# Analouge.net
KiCad netlist of a schematic drawn in Altium Designer
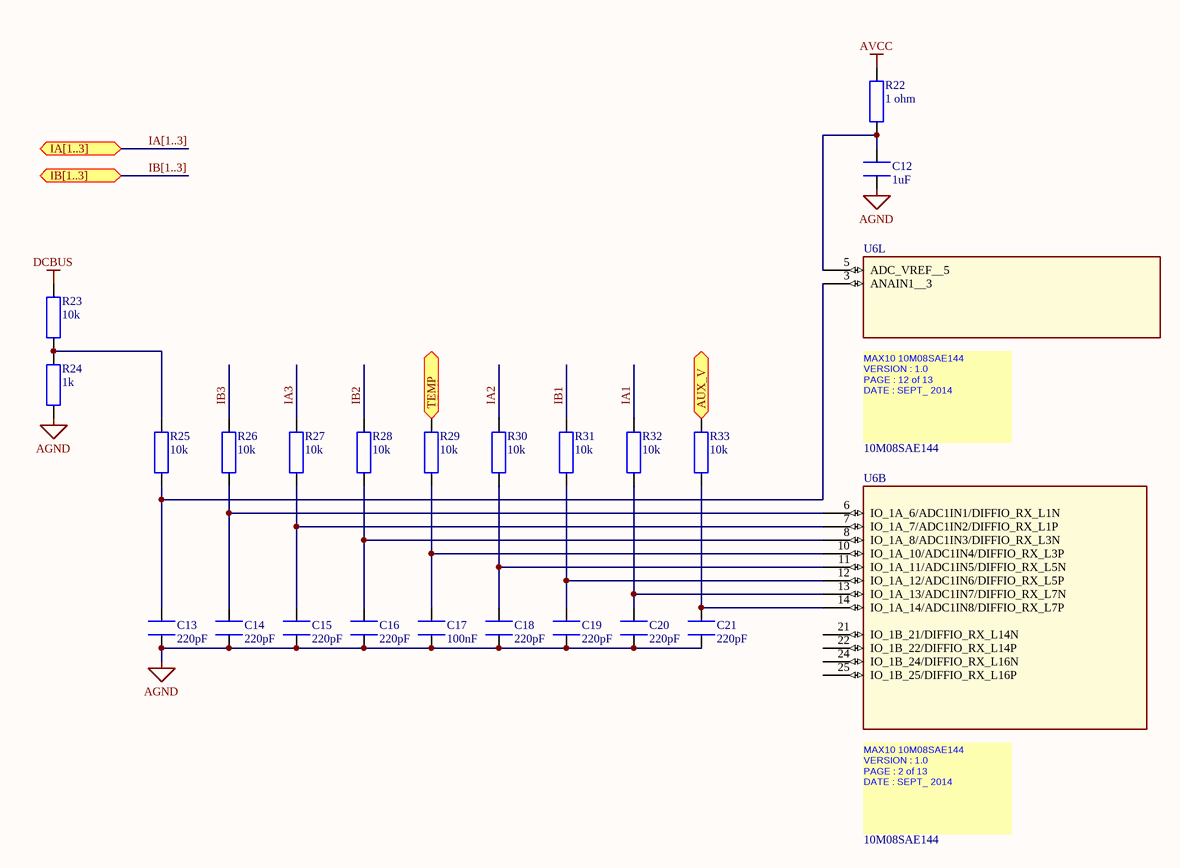
[diagram p0: Analouge.SchDoc]

(export (version "E")
  (design (tool "Eeschema 10.0.6"))
  (components
    (comp (ref "C12")
      (value "1uF")
      (footprint "1608[0603]")
      (description "CAP, MLCC, X5R, 1UF, 16V, 0603")
      (fields (field (name "Comment") "MC0603X105K160"))
      (libsource (lib "CustomComponents") (part "MC0603X105K160"))
    )
    (comp (ref "C13")
      (value "220pF")
      (footprint "1608[0603]")
      (description "CAP, MLCC, C0G/NP0, 220PF, 50V, 0603")
      (fields (field (name "Comment") "MC0603N221J500CT"))
      (libsource (lib "CustomComponents") (part "MC0603N221J500CT"))
    )
    (comp (ref "C14")
      (value "220pF")
      (footprint "1608[0603]")
      (description "CAP, MLCC, C0G/NP0, 220PF, 50V, 0603")
      (fields (field (name "Comment") "MC0603N221J500CT"))
      (libsource (lib "CustomComponents") (part "MC0603N221J500CT"))
    )
    (comp (ref "C15")
      (value "220pF")
      (footprint "1608[0603]")
      (description "CAP, MLCC, C0G/NP0, 220PF, 50V, 0603")
      (fields (field (name "Comment") "MC0603N221J500CT"))
      (libsource (lib "CustomComponents") (part "MC0603N221J500CT"))
    )
    (comp (ref "C16")
      (value "220pF")
      (footprint "1608[0603]")
      (description "CAP, MLCC, C0G/NP0, 220PF, 50V, 0603")
      (fields (field (name "Comment") "MC0603N221J500CT"))
      (libsource (lib "CustomComponents") (part "MC0603N221J500CT"))
    )
    (comp (ref "C17")
      (value "100nF")
      (footprint "1608[0603]")
      (description "CAP, MLCC, X7R, 100NF, 16V, 0603")
      (fields (field (name "Comment") "MC0603B104K160CT"))
      (libsource (lib "CustomComponents") (part "MC0603B104K160CT"))
    )
    (comp (ref "C18")
      (value "220pF")
      (footprint "1608[0603]")
      (description "CAP, MLCC, C0G/NP0, 220PF, 50V, 0603")
      (fields (field (name "Comment") "MC0603N221J500CT"))
      (libsource (lib "CustomComponents") (part "MC0603N221J500CT"))
    )
    (comp (ref "C19")
      (value "220pF")
      (footprint "1608[0603]")
      (description "CAP, MLCC, C0G/NP0, 220PF, 50V, 0603")
      (fields (field (name "Comment") "MC0603N221J500CT"))
      (libsource (lib "CustomComponents") (part "MC0603N221J500CT"))
    )
    (comp (ref "C20")
      (value "220pF")
      (footprint "1608[0603]")
      (description "CAP, MLCC, C0G/NP0, 220PF, 50V, 0603")
      (fields (field (name "Comment") "MC0603N221J500CT"))
      (libsource (lib "CustomComponents") (part "MC0603N221J500CT"))
    )
    (comp (ref "C21")
      (value "220pF")
      (footprint "1608[0603]")
      (description "CAP, MLCC, C0G/NP0, 220PF, 50V, 0603")
      (fields (field (name "Comment") "MC0603N221J500CT"))
      (libsource (lib "CustomComponents") (part "MC0603N221J500CT"))
    )
    (comp (ref "R22")
      (value "1 ohm")
      (footprint "RESC1608X55N")
      (description "RES, THICK FILM, 1OHM, 1%, 0.1W")
      (fields (field (name "Comment") "MCWR06W1R00FTL"))
      (libsource (lib "CustomComponents") (part "MCWR06W1R00FTL"))
    )
    (comp (ref "R23")
      (value "10k")
      (footprint "RESC1608X06L")
      (description "Resistor, 10k, 0603")
      (fields (field (name "Comment") "MCMR06X1002FTL"))
      (libsource (lib "CustomComponents") (part "MCMR06X1002FTL"))
    )
    (comp (ref "R24")
      (value "1k")
      (footprint "RESC1608X55N")
      (description "RESISTOR, CERAMIC, 1K, 0.1W, 1%")
      (fields (field (name "Comment") "MCMR06X1001FTL"))
      (libsource (lib "CustomComponents") (part "MCMR06X1001FTL"))
    )
    (comp (ref "R25")
      (value "10k")
      (footprint "RESC1608X06L")
      (description "Resistor, 10k, 0603")
      (fields (field (name "Comment") "MCMR06X1002FTL"))
      (libsource (lib "CustomComponents") (part "MCMR06X1002FTL"))
    )
    (comp (ref "R26")
      (value "10k")
      (footprint "RESC1608X06L")
      (description "Resistor, 10k, 0603")
      (fields (field (name "Comment") "MCMR06X1002FTL"))
      (libsource (lib "CustomComponents") (part "MCMR06X1002FTL"))
    )
    (comp (ref "R27")
      (value "10k")
      (footprint "RESC1608X06L")
      (description "Resistor, 10k, 0603")
      (fields (field (name "Comment") "MCMR06X1002FTL"))
      (libsource (lib "CustomComponents") (part "MCMR06X1002FTL"))
    )
    (comp (ref "R28")
      (value "10k")
      (footprint "RESC1608X06L")
      (description "Resistor, 10k, 0603")
      (fields (field (name "Comment") "MCMR06X1002FTL"))
      (libsource (lib "CustomComponents") (part "MCMR06X1002FTL"))
    )
    (comp (ref "R29")
      (value "10k")
      (footprint "RESC1608X06L")
      (description "Resistor, 10k, 0603")
      (fields (field (name "Comment") "MCMR06X1002FTL"))
      (libsource (lib "CustomComponents") (part "MCMR06X1002FTL"))
    )
    (comp (ref "R30")
      (value "10k")
      (footprint "RESC1608X06L")
      (description "Resistor, 10k, 0603")
      (fields (field (name "Comment") "MCMR06X1002FTL"))
      (libsource (lib "CustomComponents") (part "MCMR06X1002FTL"))
    )
    (comp (ref "R31")
      (value "10k")
      (footprint "RESC1608X06L")
      (description "Resistor, 10k, 0603")
      (fields (field (name "Comment") "MCMR06X1002FTL"))
      (libsource (lib "CustomComponents") (part "MCMR06X1002FTL"))
    )
    (comp (ref "R32")
      (value "10k")
      (footprint "RESC1608X06L")
      (description "Resistor, 10k, 0603")
      (fields (field (name "Comment") "MCMR06X1002FTL"))
      (libsource (lib "CustomComponents") (part "MCMR06X1002FTL"))
    )
    (comp (ref "R33")
      (value "10k")
      (footprint "RESC1608X06L")
      (description "Resistor, 10k, 0603")
      (fields (field (name "Comment") "MCMR06X1002FTL"))
      (libsource (lib "CustomComponents") (part "MCMR06X1002FTL"))
    )
    (comp (ref "U6")
      (value "10M08SAE144")
      (footprint "SQFP50P2200X2200X165_HS-145N")
      (libsource (lib "10M08SAREVERSIONTEST_Library") (part "10M08SAE144"))
    )
  )
  (nets
    (net (code "1") (name "/AUX_V") (class "Default")
      (node (ref "R33") (pin "2") (pinfunction "0_2") (pintype "passive"))
    )
    (net (code "2") (name "/IA1") (class "Default")
      (node (ref "R32") (pin "2") (pinfunction "0_2") (pintype "passive"))
    )
    (net (code "3") (name "/IA2") (class "Default")
      (node (ref "R30") (pin "2") (pinfunction "0_2") (pintype "passive"))
    )
    (net (code "4") (name "/IA3") (class "Default")
      (node (ref "R27") (pin "2") (pinfunction "0_2") (pintype "passive"))
    )
    (net (code "6") (name "/IB1") (class "Default")
      (node (ref "R31") (pin "2") (pinfunction "0_2") (pintype "passive"))
    )
    (net (code "7") (name "/IB2") (class "Default")
      (node (ref "R28") (pin "2") (pinfunction "0_2") (pintype "passive"))
    )
    (net (code "8") (name "/IB3") (class "Default")
      (node (ref "R26") (pin "2") (pinfunction "0_2") (pintype "passive"))
    )
    (net (code "10") (name "/TEMP") (class "Default")
      (node (ref "R29") (pin "2") (pinfunction "0_2") (pintype "passive"))
    )
    (net (code "11") (name "AGND") (class "Default")
      (node (ref "C12") (pin "1") (pinfunction "1_1") (pintype "passive"))
      (node (ref "C13") (pin "1") (pinfunction "1_1") (pintype "passive"))
      (node (ref "C14") (pin "1") (pinfunction "1_1") (pintype "passive"))
      (node (ref "C15") (pin "1") (pinfunction "1_1") (pintype "passive"))
      (node (ref "C16") (pin "1") (pinfunction "1_1") (pintype "passive"))
      (node (ref "C17") (pin "1") (pinfunction "1_1") (pintype "passive"))
      (node (ref "C18") (pin "1") (pinfunction "1_1") (pintype "passive"))
      (node (ref "C19") (pin "1") (pinfunction "1_1") (pintype "passive"))
      (node (ref "C20") (pin "1") (pinfunction "1_1") (pintype "passive"))
      (node (ref "C21") (pin "1") (pinfunction "1_1") (pintype "passive"))
      (node (ref "R24") (pin "1") (pinfunction "0_1") (pintype "passive"))
    )
    (net (code "12") (name "AVCC") (class "Default")
      (node (ref "R22") (pin "2") (pinfunction "0_2") (pintype "passive"))
    )
    (net (code "13") (name "DCBUS") (class "Default")
      (node (ref "R23") (pin "2") (pinfunction "0_2") (pintype "passive"))
    )
    (net (code "14") (name "Net-(R23-0-Pad1)") (class "Default")
      (node (ref "R23") (pin "1") (pinfunction "0_1") (pintype "passive"))
      (node (ref "R24") (pin "2") (pinfunction "0_2") (pintype "passive"))
      (node (ref "R25") (pin "2") (pinfunction "0_2") (pintype "passive"))
    )
    (net (code "15") (name "Net-(U6B-IO_1A_6{slash}ADC1IN1{slash}DIFFIO_RX_L1N)") (class "Default")
      (node (ref "C14") (pin "2") (pinfunction "2_2") (pintype "passive"))
      (node (ref "R26") (pin "1") (pinfunction "0_1") (pintype "passive"))
      (node (ref "U6") (pin "6") (pinfunction "IO_1A_6/ADC1IN1/DIFFIO_RX_L1N_6") (pintype "bidirectional"))
    )
    (net (code "16") (name "Net-(U6B-IO_1A_7{slash}ADC1IN2{slash}DIFFIO_RX_L1P)") (class "Default")
      (node (ref "C15") (pin "2") (pinfunction "2_2") (pintype "passive"))
      (node (ref "R27") (pin "1") (pinfunction "0_1") (pintype "passive"))
      (node (ref "U6") (pin "7") (pinfunction "IO_1A_7/ADC1IN2/DIFFIO_RX_L1P_7") (pintype "bidirectional"))
    )
    (net (code "17") (name "Net-(U6B-IO_1A_8{slash}ADC1IN3{slash}DIFFIO_RX_L3N)") (class "Default")
      (node (ref "C16") (pin "2") (pinfunction "2_2") (pintype "passive"))
      (node (ref "R28") (pin "1") (pinfunction "0_1") (pintype "passive"))
      (node (ref "U6") (pin "8") (pinfunction "IO_1A_8/ADC1IN3/DIFFIO_RX_L3N_8") (pintype "bidirectional"))
    )
    (net (code "18") (name "Net-(U6B-IO_1A_10{slash}ADC1IN4{slash}DIFFIO_RX_L3P)") (class "Default")
      (node (ref "C17") (pin "2") (pinfunction "2_2") (pintype "passive"))
      (node (ref "R29") (pin "1") (pinfunction "0_1") (pintype "passive"))
      (node (ref "U6") (pin "10") (pinfunction "IO_1A_10/ADC1IN4/DIFFIO_RX_L3P_10") (pintype "bidirectional"))
    )
    (net (code "19") (name "Net-(U6B-IO_1A_11{slash}ADC1IN5{slash}DIFFIO_RX_L5N)") (class "Default")
      (node (ref "C18") (pin "2") (pinfunction "2_2") (pintype "passive"))
      (node (ref "R30") (pin "1") (pinfunction "0_1") (pintype "passive"))
      (node (ref "U6") (pin "11") (pinfunction "IO_1A_11/ADC1IN5/DIFFIO_RX_L5N_11") (pintype "bidirectional"))
    )
    (net (code "20") (name "Net-(U6B-IO_1A_12{slash}ADC1IN6{slash}DIFFIO_RX_L5P)") (class "Default")
      (node (ref "C19") (pin "2") (pinfunction "2_2") (pintype "passive"))
      (node (ref "R31") (pin "1") (pinfunction "0_1") (pintype "passive"))
      (node (ref "U6") (pin "12") (pinfunction "IO_1A_12/ADC1IN6/DIFFIO_RX_L5P_12") (pintype "bidirectional"))
    )
    (net (code "21") (name "Net-(U6B-IO_1A_13{slash}ADC1IN7{slash}DIFFIO_RX_L7N)") (class "Default")
      (node (ref "C20") (pin "2") (pinfunction "2_2") (pintype "passive"))
      (node (ref "R32") (pin "1") (pinfunction "0_1") (pintype "passive"))
      (node (ref "U6") (pin "13") (pinfunction "IO_1A_13/ADC1IN7/DIFFIO_RX_L7N_13") (pintype "bidirectional"))
    )
    (net (code "22") (name "Net-(U6B-IO_1A_14{slash}ADC1IN8{slash}DIFFIO_RX_L7P)") (class "Default")
      (node (ref "C21") (pin "2") (pinfunction "2_2") (pintype "passive"))
      (node (ref "R33") (pin "1") (pinfunction "0_1") (pintype "passive"))
      (node (ref "U6") (pin "14") (pinfunction "IO_1A_14/ADC1IN8/DIFFIO_RX_L7P_14") (pintype "bidirectional"))
    )
    (net (code "23") (name "Net-(U6L-ADC_VREF__5)") (class "Default")
      (node (ref "C12") (pin "2") (pinfunction "2_2") (pintype "passive"))
      (node (ref "R22") (pin "1") (pinfunction "0_1") (pintype "passive"))
      (node (ref "U6") (pin "5") (pinfunction "ADC_VREF__5_5") (pintype "bidirectional"))
    )
    (net (code "24") (name "Net-(U6L-ANAIN1__3)") (class "Default")
      (node (ref "C13") (pin "2") (pinfunction "2_2") (pintype "passive"))
      (node (ref "R25") (pin "1") (pinfunction "0_1") (pintype "passive"))
      (node (ref "U6") (pin "3") (pinfunction "ANAIN1__3_3") (pintype "bidirectional"))
    )
    (net (code "25") (name "unconnected-(U6B-IO_1B_21{slash}DIFFIO_RX_L14N-Pad21)") (class "Default")
      (node (ref "U6") (pin "21") (pinfunction "IO_1B_21/DIFFIO_RX_L14N_21") (pintype "bidirectional"))
    )
    (net (code "26") (name "unconnected-(U6B-IO_1B_22{slash}DIFFIO_RX_L14P-Pad22)") (class "Default")
      (node (ref "U6") (pin "22") (pinfunction "IO_1B_22/DIFFIO_RX_L14P_22") (pintype "bidirectional"))
    )
    (net (code "27") (name "unconnected-(U6B-IO_1B_24{slash}DIFFIO_RX_L16N-Pad24)") (class "Default")
      (node (ref "U6") (pin "24") (pinfunction "IO_1B_24/DIFFIO_RX_L16N_24") (pintype "bidirectional"))
    )
    (net (code "28") (name "unconnected-(U6B-IO_1B_25{slash}DIFFIO_RX_L16P-Pad25)") (class "Default")
      (node (ref "U6") (pin "25") (pinfunction "IO_1B_25/DIFFIO_RX_L16P_25") (pintype "bidirectional"))
    )
  )
)
